# teensy_sync.net
KiCad netlist of a schematic drawn in EAGLE
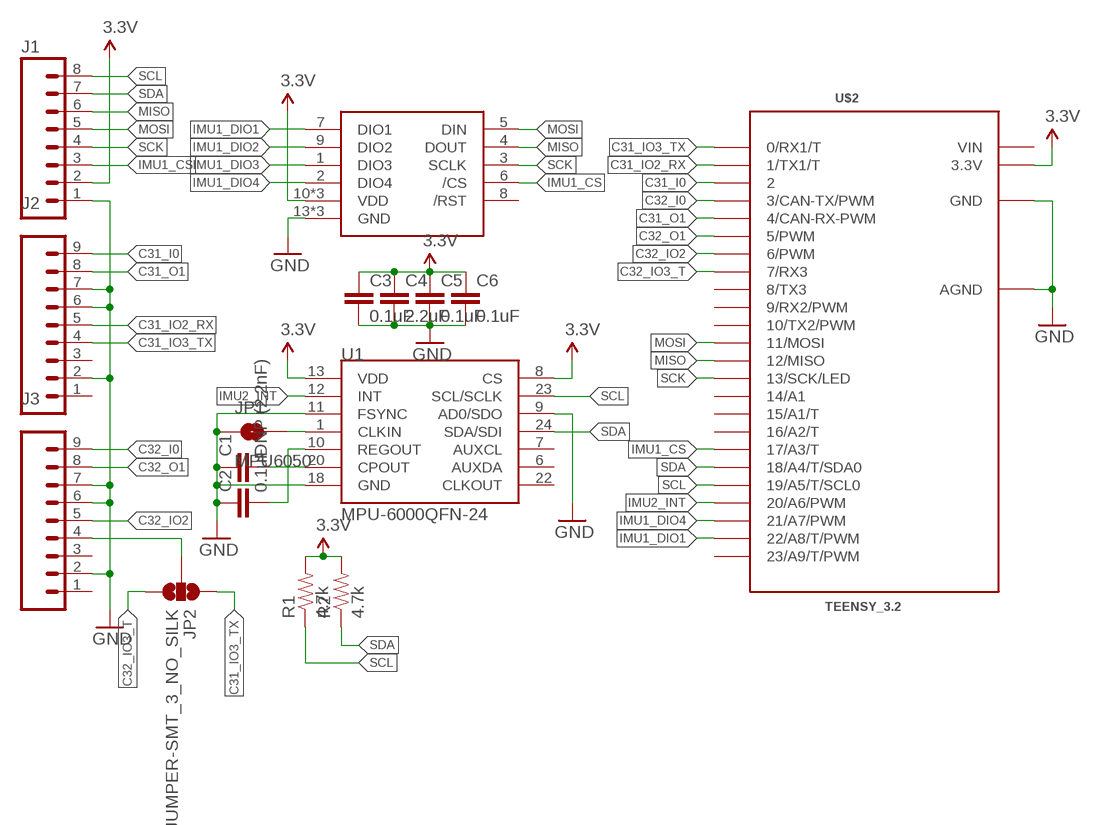
[diagram p0: schematic, sheet 1]

(export (version "E")
  (design (tool "Eeschema 10.0.6"))
  (components
    (comp (ref "C1")
      (value "DNP (2.2nF)")
      (footprint "eagle-import:0402-CAP")
      (libsource (lib "eagle-import") (part "CAP0402-CAP"))
    )
    (comp (ref "C2")
      (value "0.1uF")
      (footprint "eagle-import:0402-CAP")
      (libsource (lib "eagle-import") (part "CAP0402-CAP"))
    )
    (comp (ref "C3")
      (value "0.1uF")
      (footprint "eagle-import:0402-CAP")
      (libsource (lib "eagle-import") (part "CAP0402-CAP"))
    )
    (comp (ref "C4")
      (value "2.2uF")
      (footprint "eagle-import:0402-CAP")
      (libsource (lib "eagle-import") (part "CAP0402-CAP"))
    )
    (comp (ref "C5")
      (value "0.1uF")
      (footprint "eagle-import:0402-CAP")
      (libsource (lib "eagle-import") (part "CAP0402-CAP"))
    )
    (comp (ref "C6")
      (value "0.1uF")
      (footprint "eagle-import:0402-CAP")
      (libsource (lib "eagle-import") (part "CAP0402-CAP"))
    )
    (comp (ref "J1")
      (value "M08")
      (footprint "eagle-import:1X08_ROUND")
      (libsource (lib "eagle-import") (part "M08"))
    )
    (comp (ref "J2")
      (value "M09")
      (footprint "eagle-import:1X09")
      (libsource (lib "eagle-import") (part "M09"))
    )
    (comp (ref "J3")
      (value "M09")
      (footprint "eagle-import:1X09")
      (libsource (lib "eagle-import") (part "M09"))
    )
    (comp (ref "JP1")
      (value "MPU6050")
      (footprint "eagle-import:PAD-JUMPER-2-NO_YES_SILK")
      (libsource (lib "eagle-import") (part "JUMPER-PAD-2-NOYES_SILK"))
    )
    (comp (ref "JP2")
      (value "JUMPER-SMT_3_NO_SILK")
      (footprint "eagle-import:SMT-JUMPER_3_NO_SILK")
      (libsource (lib "eagle-import") (part "JUMPER-SMT_3_NO_SILK"))
    )
    (comp (ref "R1")
      (value "4.7k")
      (footprint "eagle-import:0603-RES")
      (libsource (lib "eagle-import") (part "RESISTOR0603"))
    )
    (comp (ref "R2")
      (value "4.7k")
      (footprint "eagle-import:0603-RES")
      (libsource (lib "eagle-import") (part "RESISTOR0603"))
    )
    (comp (ref "U$1")
      (value "ADIS16448")
      (footprint "eagle-import:ADIS16448")
      (libsource (lib "eagle-import") (part "ADIS16448"))
    )
    (comp (ref "U$2")
      (value "TEENSY_3.2")
      (footprint "eagle-import:TEENSY3-DIL")
      (libsource (lib "eagle-import") (part "TEENSY_3.1_DIL"))
    )
    (comp (ref "U1")
      (value "MPU-6000QFN-24")
      (footprint "eagle-import:QFN-24-TESTING")
      (libsource (lib "eagle-import") (part "MPU-6000QFN-24"))
    )
  )
  (nets
    (net (code "1") (name "/VIN") (class "Default")
      (node (ref "U$2") (pin "VIN") (pinfunction "VIN_VIN") (pintype "power_in"))
    )
    (net (code "2") (name "3.3V") (class "Default")
      (node (ref "C3") (pin "1") (pinfunction "1_1") (pintype "passive"))
      (node (ref "C4") (pin "1") (pinfunction "1_1") (pintype "passive"))
      (node (ref "C5") (pin "1") (pinfunction "1_1") (pintype "passive"))
      (node (ref "C6") (pin "1") (pinfunction "1_1") (pintype "passive"))
      (node (ref "J1") (pin "2") (pinfunction "2_2") (pintype "passive"))
      (node (ref "R1") (pin "2") (pinfunction "2_2") (pintype "passive"))
      (node (ref "R2") (pin "2") (pinfunction "2_2") (pintype "passive"))
      (node (ref "U$1") (pin "10") (pinfunction "VDD_10") (pintype "bidirectional"))
      (node (ref "U$1") (pin "11") (pinfunction "VDD_11") (pintype "bidirectional"))
      (node (ref "U$1") (pin "12") (pinfunction "VDD_12") (pintype "bidirectional"))
      (node (ref "U$2") (pin "3.3V") (pinfunction "3.3V_3.3V") (pintype "power_in"))
      (node (ref "U1") (pin "13") (pinfunction "VDD_13") (pintype "bidirectional"))
      (node (ref "U1") (pin "8") (pinfunction "CS_8") (pintype "bidirectional"))
    )
    (net (code "3") (name "C31_I0") (class "Default")
      (node (ref "J2") (pin "9") (pinfunction "9_9") (pintype "passive"))
      (node (ref "U$2") (pin "2") (pinfunction "2_2") (pintype "bidirectional"))
    )
    (net (code "4") (name "C31_IO2_RX") (class "Default")
      (node (ref "J2") (pin "5") (pinfunction "5_5") (pintype "passive"))
      (node (ref "U$2") (pin "1") (pinfunction "1/TX1/T_1") (pintype "bidirectional"))
    )
    (net (code "5") (name "C31_IO3_TX") (class "Default")
      (node (ref "J2") (pin "4") (pinfunction "4_4") (pintype "passive"))
      (node (ref "JP2") (pin "1") (pinfunction "1_1") (pintype "passive"))
      (node (ref "U$2") (pin "0") (pinfunction "0/RX1/T_0") (pintype "bidirectional"))
    )
    (net (code "6") (name "C31_O1") (class "Default")
      (node (ref "J2") (pin "8") (pinfunction "8_8") (pintype "passive"))
      (node (ref "U$2") (pin "4") (pinfunction "4/CAN-RX-PWM_4") (pintype "bidirectional"))
    )
    (net (code "7") (name "C32_I0") (class "Default")
      (node (ref "J3") (pin "9") (pinfunction "9_9") (pintype "passive"))
      (node (ref "U$2") (pin "3") (pinfunction "3/CAN-TX/PWM_3") (pintype "bidirectional"))
    )
    (net (code "8") (name "C32_IO2") (class "Default")
      (node (ref "J3") (pin "5") (pinfunction "5_5") (pintype "passive"))
      (node (ref "U$2") (pin "6") (pinfunction "6/PWM_6") (pintype "bidirectional"))
    )
    (net (code "9") (name "C32_IO3_T") (class "Default")
      (node (ref "JP2") (pin "3") (pinfunction "3_3") (pintype "passive"))
      (node (ref "U$2") (pin "7") (pinfunction "7/RX3_7") (pintype "bidirectional"))
    )
    (net (code "10") (name "C32_O1") (class "Default")
      (node (ref "J3") (pin "8") (pinfunction "8_8") (pintype "passive"))
      (node (ref "U$2") (pin "5") (pinfunction "5/PWM_5") (pintype "bidirectional"))
    )
    (net (code "11") (name "GND") (class "Default")
      (node (ref "C1") (pin "1") (pinfunction "1_1") (pintype "passive"))
      (node (ref "C2") (pin "1") (pinfunction "1_1") (pintype "passive"))
      (node (ref "C3") (pin "2") (pinfunction "2_2") (pintype "passive"))
      (node (ref "C4") (pin "2") (pinfunction "2_2") (pintype "passive"))
      (node (ref "C5") (pin "2") (pinfunction "2_2") (pintype "passive"))
      (node (ref "C6") (pin "2") (pinfunction "2_2") (pintype "passive"))
      (node (ref "J1") (pin "1") (pinfunction "1_1") (pintype "passive"))
      (node (ref "J2") (pin "2") (pinfunction "2_2") (pintype "passive"))
      (node (ref "J2") (pin "6") (pinfunction "6_6") (pintype "passive"))
      (node (ref "J2") (pin "7") (pinfunction "7_7") (pintype "passive"))
      (node (ref "J3") (pin "2") (pinfunction "2_2") (pintype "passive"))
      (node (ref "J3") (pin "6") (pinfunction "6_6") (pintype "passive"))
      (node (ref "J3") (pin "7") (pinfunction "7_7") (pintype "passive"))
      (node (ref "JP1") (pin "1") (pinfunction "1_1") (pintype "passive"))
      (node (ref "U$1") (pin "13") (pinfunction "GND_13") (pintype "bidirectional"))
      (node (ref "U$1") (pin "14") (pinfunction "GND_14") (pintype "bidirectional"))
      (node (ref "U$1") (pin "15") (pinfunction "GND_15") (pintype "bidirectional"))
      (node (ref "U$2") (pin "AGND") (pinfunction "AGND_AGND") (pintype "power_in"))
      (node (ref "U$2") (pin "GND") (pinfunction "GND_GND") (pintype "power_in"))
      (node (ref "U1") (pin "11") (pinfunction "FSYNC_11") (pintype "bidirectional"))
      (node (ref "U1") (pin "18") (pinfunction "GND_18") (pintype "bidirectional"))
      (node (ref "U1") (pin "9") (pinfunction "AD0/SDO_9") (pintype "bidirectional"))
    )
    (net (code "12") (name "IMU1_CS") (class "Default")
      (node (ref "J1") (pin "3") (pinfunction "3_3") (pintype "passive"))
      (node (ref "U$1") (pin "6") (pinfunction "/CS_6") (pintype "bidirectional"))
      (node (ref "U$2") (pin "17/A3") (pinfunction "17/A3/T_17/A3") (pintype "bidirectional"))
    )
    (net (code "13") (name "IMU1_DIO1") (class "Default")
      (node (ref "U$1") (pin "7") (pinfunction "DIO1_7") (pintype "bidirectional"))
      (node (ref "U$2") (pin "22/A8") (pinfunction "22/A8/T/PWM_22/A8") (pintype "bidirectional"))
    )
    (net (code "14") (name "IMU1_DIO2") (class "Default")
      (node (ref "U$1") (pin "9") (pinfunction "DIO2_9") (pintype "bidirectional"))
    )
    (net (code "15") (name "IMU1_DIO3") (class "Default")
      (node (ref "U$1") (pin "1") (pinfunction "DIO3_1") (pintype "bidirectional"))
    )
    (net (code "16") (name "IMU1_DIO4") (class "Default")
      (node (ref "U$1") (pin "2") (pinfunction "DIO4_2") (pintype "bidirectional"))
      (node (ref "U$2") (pin "21/A7") (pinfunction "21/A7/PWM_21/A7") (pintype "bidirectional"))
    )
    (net (code "17") (name "IMU2_INT") (class "Default")
      (node (ref "U$2") (pin "20/A6") (pinfunction "20/A6/PWM_20/A6") (pintype "bidirectional"))
      (node (ref "U1") (pin "12") (pinfunction "INT_12") (pintype "bidirectional"))
    )
    (net (code "18") (name "MISO") (class "Default")
      (node (ref "J1") (pin "6") (pinfunction "6_6") (pintype "passive"))
      (node (ref "U$1") (pin "4") (pinfunction "DOUT_4") (pintype "bidirectional"))
      (node (ref "U$2") (pin "12") (pinfunction "12/MISO_12") (pintype "bidirectional"))
    )
    (net (code "19") (name "MOSI") (class "Default")
      (node (ref "J1") (pin "5") (pinfunction "5_5") (pintype "passive"))
      (node (ref "U$1") (pin "5") (pinfunction "DIN_5") (pintype "bidirectional"))
      (node (ref "U$2") (pin "11") (pinfunction "11/MOSI_11") (pintype "bidirectional"))
    )
    (net (code "20") (name "Net-(J3-Pad4)") (class "Default")
      (node (ref "J3") (pin "4") (pinfunction "4_4") (pintype "passive"))
      (node (ref "JP2") (pin "2") (pinfunction "2_2") (pintype "passive"))
    )
    (net (code "21") (name "Net-(U1-CLKIN)") (class "Default")
      (node (ref "JP1") (pin "2") (pinfunction "2_2") (pintype "passive"))
      (node (ref "U1") (pin "1") (pinfunction "CLKIN_1") (pintype "bidirectional"))
    )
    (net (code "22") (name "Net-(U1-CPOUT)") (class "Default")
      (node (ref "C1") (pin "2") (pinfunction "2_2") (pintype "passive"))
      (node (ref "U1") (pin "20") (pinfunction "CPOUT_20") (pintype "bidirectional"))
    )
    (net (code "23") (name "Net-(U1-REGOUT)") (class "Default")
      (node (ref "C2") (pin "2") (pinfunction "2_2") (pintype "passive"))
      (node (ref "U1") (pin "10") (pinfunction "REGOUT_10") (pintype "bidirectional"))
    )
    (net (code "24") (name "SCK") (class "Default")
      (node (ref "J1") (pin "4") (pinfunction "4_4") (pintype "passive"))
      (node (ref "U$1") (pin "3") (pinfunction "SCLK_3") (pintype "bidirectional"))
      (node (ref "U$2") (pin "13") (pinfunction "13/SCK/LED_13") (pintype "bidirectional"))
    )
    (net (code "25") (name "SCL") (class "Default")
      (node (ref "J1") (pin "8") (pinfunction "8_8") (pintype "passive"))
      (node (ref "R1") (pin "1") (pinfunction "1_1") (pintype "passive"))
      (node (ref "U$2") (pin "19/A5") (pinfunction "19/A5/T/SCL0_19/A5") (pintype "bidirectional"))
      (node (ref "U1") (pin "23") (pinfunction "SCL/SCLK_23") (pintype "bidirectional"))
    )
    (net (code "26") (name "SDA") (class "Default")
      (node (ref "J1") (pin "7") (pinfunction "7_7") (pintype "passive"))
      (node (ref "R2") (pin "1") (pinfunction "1_1") (pintype "passive"))
      (node (ref "U$2") (pin "18/A4") (pinfunction "18/A4/T/SDA0_18/A4") (pintype "bidirectional"))
      (node (ref "U1") (pin "24") (pinfunction "SDA/SDI_24") (pintype "bidirectional"))
    )
    (net (code "27") (name "unconnected-(J2-Pad1)") (class "Default")
      (node (ref "J2") (pin "1") (pinfunction "1_1") (pintype "passive"))
    )
    (net (code "28") (name "unconnected-(J2-Pad3)") (class "Default")
      (node (ref "J2") (pin "3") (pinfunction "3_3") (pintype "passive"))
    )
    (net (code "29") (name "unconnected-(J3-Pad1)") (class "Default")
      (node (ref "J3") (pin "1") (pinfunction "1_1") (pintype "passive"))
    )
    (net (code "30") (name "unconnected-(J3-Pad3)") (class "Default")
      (node (ref "J3") (pin "3") (pinfunction "3_3") (pintype "passive"))
    )
    (net (code "31") (name "unconnected-(U$1-{slash}RST-Pad8)") (class "Default")
      (node (ref "U$1") (pin "8") (pinfunction "/RST_8") (pintype "bidirectional"))
    )
    (net (code "32") (name "unconnected-(U$2-8{slash}TX3-Pad8)") (class "Default")
      (node (ref "U$2") (pin "8") (pinfunction "8/TX3_8") (pintype "bidirectional"))
    )
    (net (code "33") (name "unconnected-(U$2-9{slash}RX2{slash}PWM-Pad9)") (class "Default")
      (node (ref "U$2") (pin "9") (pinfunction "9/RX2/PWM_9") (pintype "bidirectional"))
    )
    (net (code "34") (name "unconnected-(U$2-10{slash}TX2{slash}PWM-Pad10)") (class "Default")
      (node (ref "U$2") (pin "10") (pinfunction "10/TX2/PWM_10") (pintype "bidirectional"))
    )
    (net (code "35") (name "unconnected-(U$2-14{slash}A1-Pad14{slash}A0)") (class "Default")
      (node (ref "U$2") (pin "14/A0") (pinfunction "14/A1_14/A0") (pintype "bidirectional"))
    )
    (net (code "36") (name "unconnected-(U$2-15{slash}A1{slash}T-Pad15{slash}A1)") (class "Default")
      (node (ref "U$2") (pin "15/A1") (pinfunction "15/A1/T_15/A1") (pintype "bidirectional"))
    )
    (net (code "37") (name "unconnected-(U$2-16{slash}A2{slash}T-Pad16{slash}A2)") (class "Default")
      (node (ref "U$2") (pin "16/A2") (pinfunction "16/A2/T_16/A2") (pintype "bidirectional"))
    )
    (net (code "38") (name "unconnected-(U$2-23{slash}A9{slash}T{slash}PWM-Pad23{slash}A9)") (class "Default")
      (node (ref "U$2") (pin "23/A9") (pinfunction "23/A9/T/PWM_23/A9") (pintype "bidirectional"))
    )
    (net (code "39") (name "unconnected-(U1-AUXCL-Pad7)") (class "Default")
      (node (ref "U1") (pin "7") (pinfunction "AUXCL_7") (pintype "bidirectional"))
    )
    (net (code "40") (name "unconnected-(U1-AUXDA-Pad6)") (class "Default")
      (node (ref "U1") (pin "6") (pinfunction "AUXDA_6") (pintype "bidirectional"))
    )
    (net (code "41") (name "unconnected-(U1-CLKOUT-Pad22)") (class "Default")
      (node (ref "U1") (pin "22") (pinfunction "CLKOUT_22") (pintype "bidirectional"))
    )
  )
)
